# GPduino-R.net
KiCad netlist of a schematic drawn in EAGLE
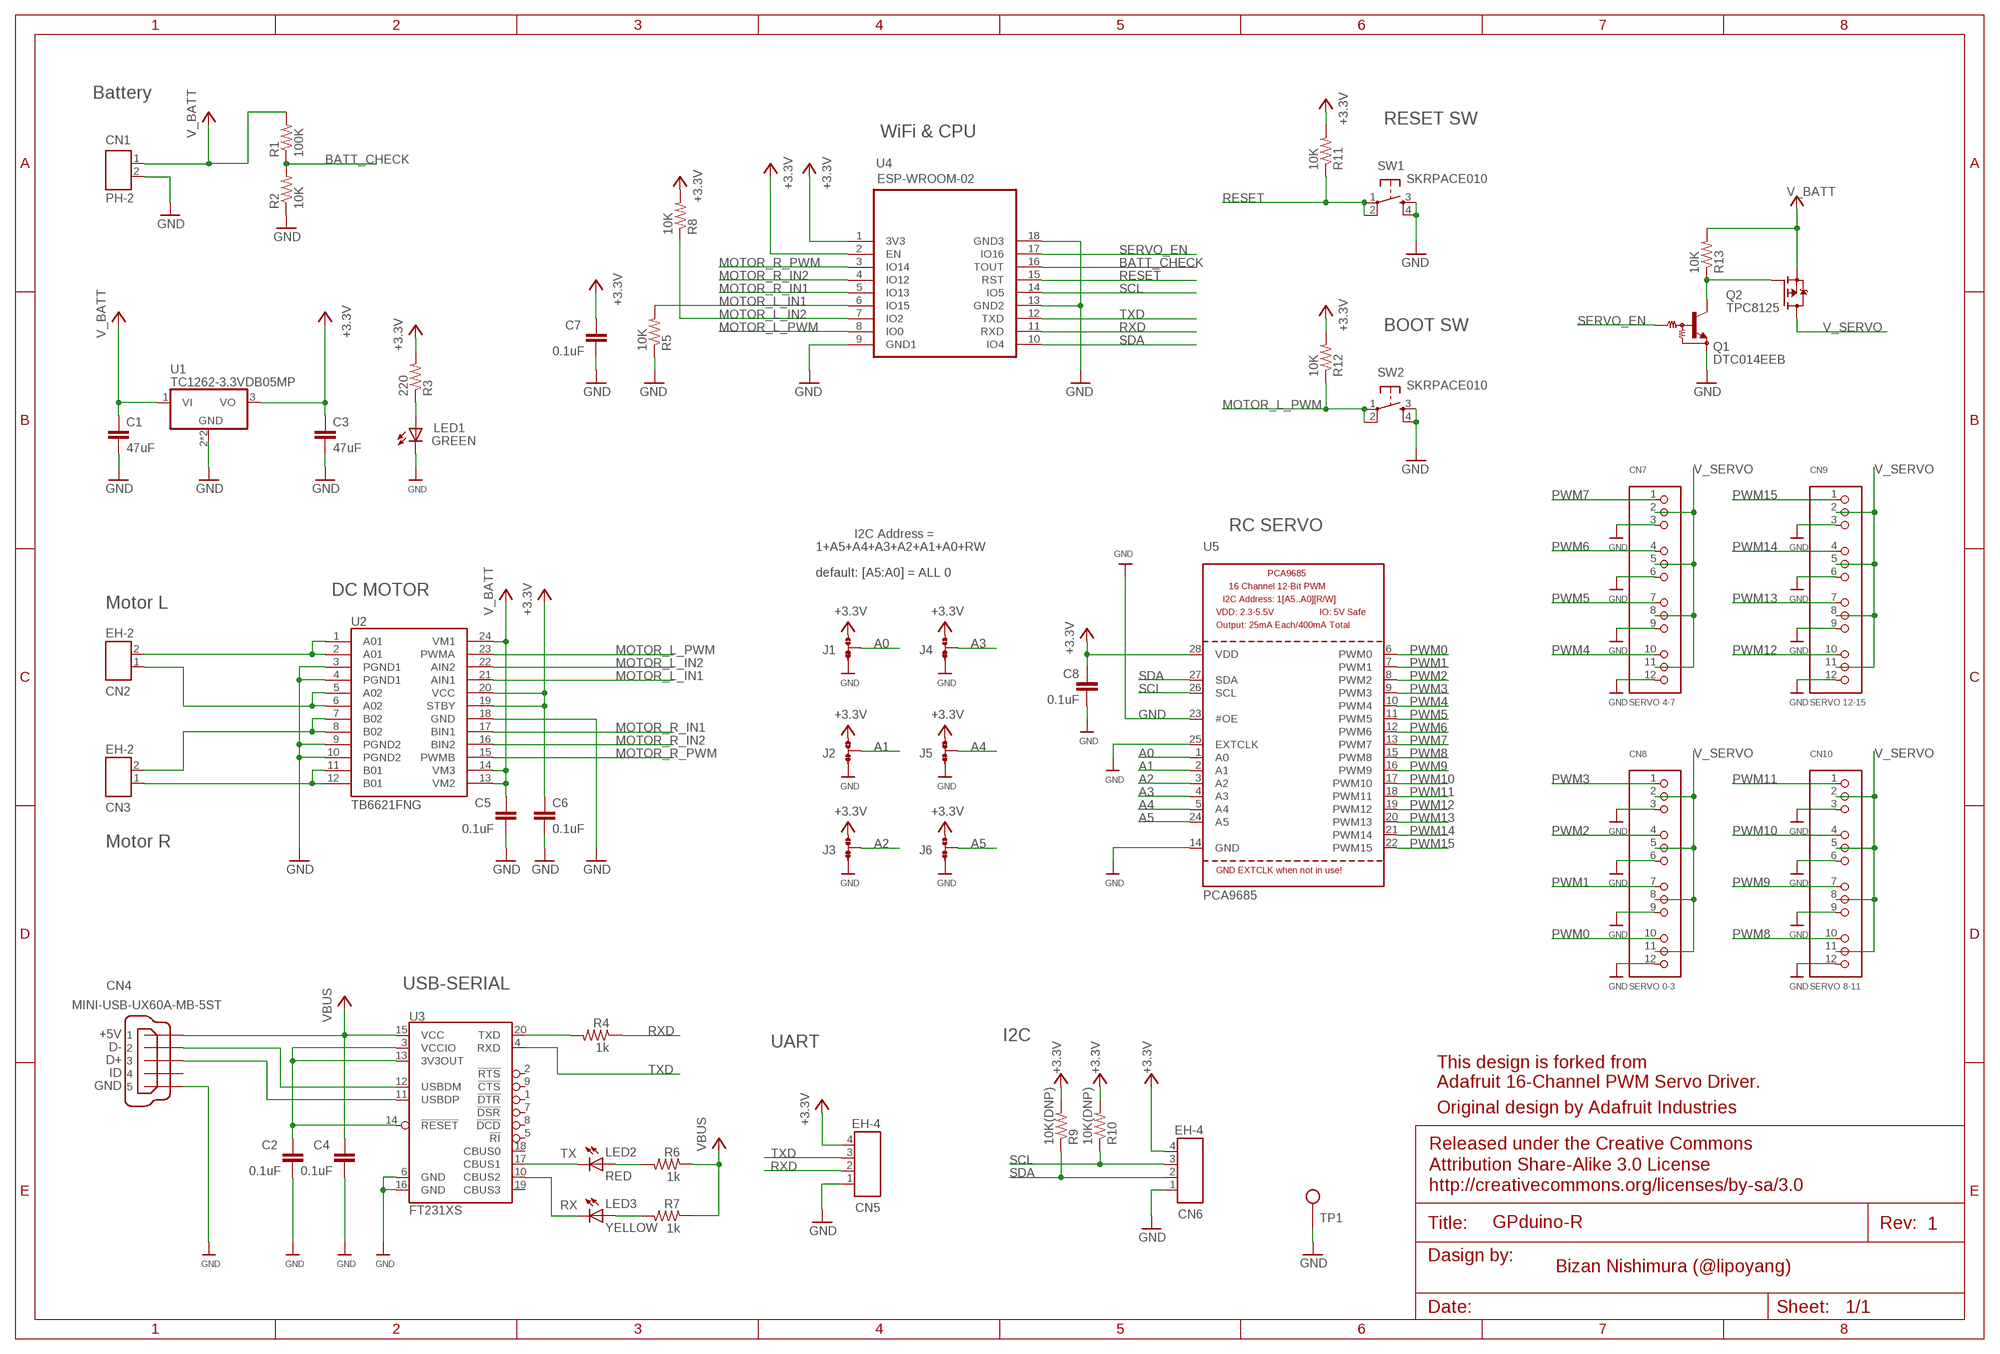
[diagram p0: schematic, sheet 1]

(export (version "E")
  (design (tool "Eeschema 10.0.6"))
  (components
    (comp (ref "C1")
      (value "47uF")
      (footprint "eagle-import:C3216")
      (libsource (lib "eagle-import") (part "C-EUC3216"))
    )
    (comp (ref "C2")
      (value "0.1uF")
      (footprint "eagle-import:C1608")
      (libsource (lib "eagle-import") (part "C-EUC1608"))
    )
    (comp (ref "C3")
      (value "47uF")
      (footprint "eagle-import:C3216")
      (libsource (lib "eagle-import") (part "C-EUC3216"))
    )
    (comp (ref "C4")
      (value "0.1uF")
      (footprint "eagle-import:C1608")
      (libsource (lib "eagle-import") (part "C-EUC1608"))
    )
    (comp (ref "C5")
      (value "0.1uF")
      (footprint "eagle-import:C1608")
      (libsource (lib "eagle-import") (part "C-EUC1608"))
    )
    (comp (ref "C6")
      (value "0.1uF")
      (footprint "eagle-import:C1608")
      (libsource (lib "eagle-import") (part "C-EUC1608"))
    )
    (comp (ref "C7")
      (value "0.1uF")
      (footprint "eagle-import:C1608")
      (libsource (lib "eagle-import") (part "C-EUC1608"))
    )
    (comp (ref "C8")
      (value "0.1uF")
      (footprint "eagle-import:C1608")
      (libsource (lib "eagle-import") (part "C-EUC1608"))
    )
    (comp (ref "CN1")
      (value "PH-2")
      (footprint "eagle-import:PH-2")
      (libsource (lib "eagle-import") (part "PH-2"))
    )
    (comp (ref "CN2")
      (value "EH-2")
      (footprint "eagle-import:EH-2")
      (libsource (lib "eagle-import") (part "EH-2"))
    )
    (comp (ref "CN3")
      (value "EH-2")
      (footprint "eagle-import:EH-2")
      (libsource (lib "eagle-import") (part "EH-2"))
    )
    (comp (ref "CN4")
      (value "MINI-USB-UX60A-MB-5ST")
      (footprint "eagle-import:UX60A-MB-5ST")
      (libsource (lib "eagle-import") (part "MINI-USB-UX60A-MB-5ST"))
    )
    (comp (ref "CN5")
      (value "EH-4")
      (footprint "eagle-import:EH-4")
      (libsource (lib "eagle-import") (part "EH-4"))
    )
    (comp (ref "CN6")
      (value "EH-4")
      (footprint "eagle-import:EH-4")
      (libsource (lib "eagle-import") (part "EH-4"))
    )
    (comp (ref "CN7")
      (value "SERVO 4-7")
      (footprint "eagle-import:3X04")
      (libsource (lib "eagle-import") (part "HEADER-3X04"))
    )
    (comp (ref "CN8")
      (value "SERVO 0-3")
      (footprint "eagle-import:3X04")
      (libsource (lib "eagle-import") (part "HEADER-3X04"))
    )
    (comp (ref "CN9")
      (value "SERVO 12-15")
      (footprint "eagle-import:3X04")
      (libsource (lib "eagle-import") (part "HEADER-3X04"))
    )
    (comp (ref "CN10")
      (value "SERVO 8-11")
      (footprint "eagle-import:3X04")
      (libsource (lib "eagle-import") (part "HEADER-3X04"))
    )
    (comp (ref "J1")
      (value "JUMP-SHORTB")
      (footprint "eagle-import:JUMP-SHORT")
      (libsource (lib "eagle-import") (part "JUMP-SHORTB"))
    )
    (comp (ref "J2")
      (value "JUMP-SHORTB")
      (footprint "eagle-import:JUMP-SHORT")
      (libsource (lib "eagle-import") (part "JUMP-SHORTB"))
    )
    (comp (ref "J3")
      (value "JUMP-SHORTB")
      (footprint "eagle-import:JUMP-SHORT")
      (libsource (lib "eagle-import") (part "JUMP-SHORTB"))
    )
    (comp (ref "J4")
      (value "JUMP-SHORTB")
      (footprint "eagle-import:JUMP-SHORT")
      (libsource (lib "eagle-import") (part "JUMP-SHORTB"))
    )
    (comp (ref "J5")
      (value "JUMP-SHORTB")
      (footprint "eagle-import:JUMP-SHORT")
      (libsource (lib "eagle-import") (part "JUMP-SHORTB"))
    )
    (comp (ref "J6")
      (value "JUMP-SHORTB")
      (footprint "eagle-import:JUMP-SHORT")
      (libsource (lib "eagle-import") (part "JUMP-SHORTB"))
    )
    (comp (ref "LED1")
      (value "GREEN")
      (footprint "eagle-import:CHIPLED_0603")
      (libsource (lib "eagle-import") (part "LEDCHIPLED_0603"))
    )
    (comp (ref "LED2")
      (value "RED")
      (footprint "eagle-import:CHIPLED_0603")
      (libsource (lib "eagle-import") (part "LEDCHIPLED_0603"))
    )
    (comp (ref "LED3")
      (value "YELLOW")
      (footprint "eagle-import:CHIPLED_0603")
      (libsource (lib "eagle-import") (part "LEDCHIPLED_0603"))
    )
    (comp (ref "Q1")
      (value "DTC014EEB")
      (footprint "eagle-import:SOT490")
      (libsource (lib "eagle-import") (part "DIGITORASC89"))
    )
    (comp (ref "Q2")
      (value "TPC8125")
      (footprint "eagle-import:SO-8")
      (libsource (lib "eagle-import") (part "TPC8125"))
    )
    (comp (ref "R1")
      (value "100K")
      (footprint "eagle-import:0603-RES")
      (libsource (lib "eagle-import") (part "RESISTOR0603-RES"))
    )
    (comp (ref "R2")
      (value "10K")
      (footprint "eagle-import:0603-RES")
      (libsource (lib "eagle-import") (part "RESISTOR0603-RES"))
    )
    (comp (ref "R3")
      (value "220")
      (footprint "eagle-import:0603-RES")
      (libsource (lib "eagle-import") (part "RESISTOR0603-RES"))
    )
    (comp (ref "R4")
      (value "1k")
      (footprint "eagle-import:0603-RES")
      (libsource (lib "eagle-import") (part "RESISTOR0603-RES"))
    )
    (comp (ref "R5")
      (value "10K")
      (footprint "eagle-import:0603-RES")
      (libsource (lib "eagle-import") (part "RESISTOR0603-RES"))
    )
    (comp (ref "R6")
      (value "1k")
      (footprint "eagle-import:0603-RES")
      (libsource (lib "eagle-import") (part "RESISTOR0603-RES"))
    )
    (comp (ref "R7")
      (value "1k")
      (footprint "eagle-import:0603-RES")
      (libsource (lib "eagle-import") (part "RESISTOR0603-RES"))
    )
    (comp (ref "R8")
      (value "10K")
      (footprint "eagle-import:0603-RES")
      (libsource (lib "eagle-import") (part "RESISTOR0603-RES"))
    )
    (comp (ref "R9")
      (value "10K(DNP)")
      (footprint "eagle-import:0603-RES")
      (libsource (lib "eagle-import") (part "RESISTOR0603-RES"))
    )
    (comp (ref "R10")
      (value "10K(DNP)")
      (footprint "eagle-import:0603-RES")
      (libsource (lib "eagle-import") (part "RESISTOR0603-RES"))
    )
    (comp (ref "R11")
      (value "10K")
      (footprint "eagle-import:0603-RES")
      (libsource (lib "eagle-import") (part "RESISTOR0603-RES"))
    )
    (comp (ref "R12")
      (value "10K")
      (footprint "eagle-import:0603-RES")
      (libsource (lib "eagle-import") (part "RESISTOR0603-RES"))
    )
    (comp (ref "R13")
      (value "10K")
      (footprint "eagle-import:0603-RES")
      (libsource (lib "eagle-import") (part "RESISTOR0603-RES"))
    )
    (comp (ref "SW1")
      (value "SKRPACE010")
      (footprint "eagle-import:SKRPACE010")
      (libsource (lib "eagle-import") (part "SKRPACE010"))
    )
    (comp (ref "SW2")
      (value "SKRPACE010")
      (footprint "eagle-import:SKRPACE010")
      (libsource (lib "eagle-import") (part "SKRPACE010"))
    )
    (comp (ref "TP1")
      (value "TEST_PIN")
      (footprint "eagle-import:TEST_PIN")
      (libsource (lib "eagle-import") (part "TEST_PIN"))
    )
    (comp (ref "U1")
      (value "TC1262-3.3VDB05MP")
      (footprint "eagle-import:SOT223")
      (libsource (lib "eagle-import") (part "TC1262-3.3VDBMP05"))
    )
    (comp (ref "U2")
      (value "TB6621FNG")
      (footprint "eagle-import:SSOP24")
      (libsource (lib "eagle-import") (part "TB6621FNG"))
    )
    (comp (ref "U3")
      (value "FT231XS")
      (footprint "eagle-import:SSOP20")
      (libsource (lib "eagle-import") (part "FT231XS"))
    )
    (comp (ref "U4")
      (value "ESP-WROOM-02")
      (footprint "eagle-import:FRONT-FACE")
      (libsource (lib "eagle-import") (part "ESP-WROOM-02FRONT-FACE"))
    )
    (comp (ref "U5")
      (value "PCA9685")
      (footprint "eagle-import:TSSOP28")
      (libsource (lib "eagle-import") (part "PCA9685"))
    )
  )
  (nets
    (net (code "1") (name "+3.3V") (class "Default")
      (node (ref "C3") (pin "1") (pinfunction "1_1") (pintype "passive"))
      (node (ref "C6") (pin "1") (pinfunction "1_1") (pintype "passive"))
      (node (ref "C7") (pin "1") (pinfunction "1_1") (pintype "passive"))
      (node (ref "C8") (pin "1") (pinfunction "1_1") (pintype "passive"))
      (node (ref "CN5") (pin "4") (pinfunction "4_4") (pintype "bidirectional"))
      (node (ref "CN6") (pin "4") (pinfunction "4_4") (pintype "bidirectional"))
      (node (ref "J1") (pin "1") (pinfunction "1_1") (pintype "passive"))
      (node (ref "J2") (pin "1") (pinfunction "1_1") (pintype "passive"))
      (node (ref "J3") (pin "1") (pinfunction "1_1") (pintype "passive"))
      (node (ref "J4") (pin "1") (pinfunction "1_1") (pintype "passive"))
      (node (ref "J5") (pin "1") (pinfunction "1_1") (pintype "passive"))
      (node (ref "J6") (pin "1") (pinfunction "1_1") (pintype "passive"))
      (node (ref "R10") (pin "2") (pinfunction "2_2") (pintype "passive"))
      (node (ref "R11") (pin "2") (pinfunction "2_2") (pintype "passive"))
      (node (ref "R12") (pin "2") (pinfunction "2_2") (pintype "passive"))
      (node (ref "R3") (pin "2") (pinfunction "2_2") (pintype "passive"))
      (node (ref "R8") (pin "2") (pinfunction "2_2") (pintype "passive"))
      (node (ref "R9") (pin "2") (pinfunction "2_2") (pintype "passive"))
      (node (ref "U1") (pin "3") (pinfunction "VO_3") (pintype "passive"))
      (node (ref "U2") (pin "19") (pinfunction "STBY_19") (pintype "bidirectional"))
      (node (ref "U2") (pin "20") (pinfunction "VCC_20") (pintype "bidirectional"))
      (node (ref "U4") (pin "1") (pinfunction "3V3_1") (pintype "power_in"))
      (node (ref "U4") (pin "2") (pinfunction "EN_2") (pintype "bidirectional"))
      (node (ref "U5") (pin "28") (pinfunction "VDD_28") (pintype "power_in"))
    )
    (net (code "2") (name "/A0") (class "Default")
      (node (ref "J1") (pin "2") (pinfunction "2_2") (pintype "passive"))
      (node (ref "U5") (pin "1") (pinfunction "A0_1") (pintype "bidirectional"))
    )
    (net (code "3") (name "/A1") (class "Default")
      (node (ref "J2") (pin "2") (pinfunction "2_2") (pintype "passive"))
      (node (ref "U5") (pin "2") (pinfunction "A1_2") (pintype "bidirectional"))
    )
    (net (code "4") (name "/A2") (class "Default")
      (node (ref "J3") (pin "2") (pinfunction "2_2") (pintype "passive"))
      (node (ref "U5") (pin "3") (pinfunction "A2_3") (pintype "bidirectional"))
    )
    (net (code "5") (name "/A3") (class "Default")
      (node (ref "J4") (pin "2") (pinfunction "2_2") (pintype "passive"))
      (node (ref "U5") (pin "4") (pinfunction "A3_4") (pintype "bidirectional"))
    )
    (net (code "6") (name "/A4") (class "Default")
      (node (ref "J5") (pin "2") (pinfunction "2_2") (pintype "passive"))
      (node (ref "U5") (pin "5") (pinfunction "A4_5") (pintype "bidirectional"))
    )
    (net (code "7") (name "/A5") (class "Default")
      (node (ref "J6") (pin "2") (pinfunction "2_2") (pintype "passive"))
      (node (ref "U5") (pin "24") (pinfunction "A5_24") (pintype "bidirectional"))
    )
    (net (code "8") (name "/BATT_CHECK") (class "Default")
      (node (ref "R1") (pin "1") (pinfunction "1_1") (pintype "passive"))
      (node (ref "R2") (pin "2") (pinfunction "2_2") (pintype "passive"))
      (node (ref "U4") (pin "16") (pinfunction "TOUT_16") (pintype "bidirectional"))
    )
    (net (code "9") (name "/MOTOR_L_IN1") (class "Default")
      (node (ref "R5") (pin "2") (pinfunction "2_2") (pintype "passive"))
      (node (ref "U2") (pin "21") (pinfunction "AIN1_21") (pintype "bidirectional"))
      (node (ref "U4") (pin "6") (pinfunction "IO15_6") (pintype "bidirectional"))
    )
    (net (code "10") (name "/MOTOR_L_IN2") (class "Default")
      (node (ref "R8") (pin "1") (pinfunction "1_1") (pintype "passive"))
      (node (ref "U2") (pin "22") (pinfunction "AIN2_22") (pintype "bidirectional"))
      (node (ref "U4") (pin "7") (pinfunction "IO2_7") (pintype "bidirectional"))
    )
    (net (code "11") (name "/MOTOR_L_PWM") (class "Default")
      (node (ref "R12") (pin "1") (pinfunction "1_1") (pintype "passive"))
      (node (ref "SW2") (pin "1") (pinfunction "1_1") (pintype "passive"))
      (node (ref "SW2") (pin "2") (pinfunction "2_2") (pintype "passive"))
      (node (ref "U2") (pin "23") (pinfunction "PWMA_23") (pintype "bidirectional"))
      (node (ref "U4") (pin "8") (pinfunction "IO0_8") (pintype "bidirectional"))
    )
    (net (code "12") (name "/MOTOR_R_IN1") (class "Default")
      (node (ref "U2") (pin "17") (pinfunction "BIN1_17") (pintype "bidirectional"))
      (node (ref "U4") (pin "5") (pinfunction "IO13_5") (pintype "bidirectional"))
    )
    (net (code "13") (name "/MOTOR_R_IN2") (class "Default")
      (node (ref "U2") (pin "16") (pinfunction "BIN2_16") (pintype "bidirectional"))
      (node (ref "U4") (pin "4") (pinfunction "IO12_4") (pintype "bidirectional"))
    )
    (net (code "14") (name "/MOTOR_R_PWM") (class "Default")
      (node (ref "U2") (pin "15") (pinfunction "PWMB_15") (pintype "bidirectional"))
      (node (ref "U4") (pin "3") (pinfunction "IO14_3") (pintype "bidirectional"))
    )
    (net (code "15") (name "/PWM0") (class "Default")
      (node (ref "CN8") (pin "10") (pinfunction "10_10") (pintype "passive"))
      (node (ref "U5") (pin "6") (pinfunction "PWM0_6") (pintype "output"))
    )
    (net (code "16") (name "/PWM1") (class "Default")
      (node (ref "CN8") (pin "7") (pinfunction "7_7") (pintype "passive"))
      (node (ref "U5") (pin "7") (pinfunction "PWM1_7") (pintype "output"))
    )
    (net (code "17") (name "/PWM2") (class "Default")
      (node (ref "CN8") (pin "4") (pinfunction "4_4") (pintype "passive"))
      (node (ref "U5") (pin "8") (pinfunction "PWM2_8") (pintype "output"))
    )
    (net (code "18") (name "/PWM3") (class "Default")
      (node (ref "CN8") (pin "1") (pinfunction "1_1") (pintype "passive"))
      (node (ref "U5") (pin "9") (pinfunction "PWM3_9") (pintype "output"))
    )
    (net (code "19") (name "/PWM4") (class "Default")
      (node (ref "CN7") (pin "10") (pinfunction "10_10") (pintype "passive"))
      (node (ref "U5") (pin "10") (pinfunction "PWM4_10") (pintype "output"))
    )
    (net (code "20") (name "/PWM5") (class "Default")
      (node (ref "CN7") (pin "7") (pinfunction "7_7") (pintype "passive"))
      (node (ref "U5") (pin "11") (pinfunction "PWM5_11") (pintype "output"))
    )
    (net (code "21") (name "/PWM6") (class "Default")
      (node (ref "CN7") (pin "4") (pinfunction "4_4") (pintype "passive"))
      (node (ref "U5") (pin "12") (pinfunction "PWM6_12") (pintype "output"))
    )
    (net (code "22") (name "/PWM7") (class "Default")
      (node (ref "CN7") (pin "1") (pinfunction "1_1") (pintype "passive"))
      (node (ref "U5") (pin "13") (pinfunction "PWM7_13") (pintype "output"))
    )
    (net (code "23") (name "/PWM8") (class "Default")
      (node (ref "CN10") (pin "10") (pinfunction "10_10") (pintype "passive"))
      (node (ref "U5") (pin "15") (pinfunction "PWM8_15") (pintype "output"))
    )
    (net (code "24") (name "/PWM9") (class "Default")
      (node (ref "CN10") (pin "7") (pinfunction "7_7") (pintype "passive"))
      (node (ref "U5") (pin "16") (pinfunction "PWM9_16") (pintype "output"))
    )
    (net (code "25") (name "/PWM10") (class "Default")
      (node (ref "CN10") (pin "4") (pinfunction "4_4") (pintype "passive"))
      (node (ref "U5") (pin "17") (pinfunction "PWM10_17") (pintype "output"))
    )
    (net (code "26") (name "/PWM11") (class "Default")
      (node (ref "CN10") (pin "1") (pinfunction "1_1") (pintype "passive"))
      (node (ref "U5") (pin "18") (pinfunction "PWM11_18") (pintype "output"))
    )
    (net (code "27") (name "/PWM12") (class "Default")
      (node (ref "CN9") (pin "10") (pinfunction "10_10") (pintype "passive"))
      (node (ref "U5") (pin "19") (pinfunction "PWM12_19") (pintype "output"))
    )
    (net (code "28") (name "/PWM13") (class "Default")
      (node (ref "CN9") (pin "7") (pinfunction "7_7") (pintype "passive"))
      (node (ref "U5") (pin "20") (pinfunction "PWM13_20") (pintype "output"))
    )
    (net (code "29") (name "/PWM14") (class "Default")
      (node (ref "CN9") (pin "4") (pinfunction "4_4") (pintype "passive"))
      (node (ref "U5") (pin "21") (pinfunction "PWM14_21") (pintype "output"))
    )
    (net (code "30") (name "/PWM15") (class "Default")
      (node (ref "CN9") (pin "1") (pinfunction "1_1") (pintype "passive"))
      (node (ref "U5") (pin "22") (pinfunction "PWM15_22") (pintype "output"))
    )
    (net (code "31") (name "/RESET") (class "Default")
      (node (ref "R11") (pin "1") (pinfunction "1_1") (pintype "passive"))
      (node (ref "SW1") (pin "1") (pinfunction "1_1") (pintype "passive"))
      (node (ref "SW1") (pin "2") (pinfunction "2_2") (pintype "passive"))
      (node (ref "U4") (pin "15") (pinfunction "RST_15") (pintype "bidirectional"))
    )
    (net (code "32") (name "/RXD") (class "Default")
      (node (ref "CN5") (pin "2") (pinfunction "2_2") (pintype "bidirectional"))
      (node (ref "R4") (pin "1") (pinfunction "1_1") (pintype "passive"))
      (node (ref "U4") (pin "11") (pinfunction "RXD_11") (pintype "bidirectional"))
    )
    (net (code "33") (name "/SCL") (class "Default")
      (node (ref "CN6") (pin "3") (pinfunction "3_3") (pintype "bidirectional"))
      (node (ref "R10") (pin "1") (pinfunction "1_1") (pintype "passive"))
      (node (ref "U4") (pin "14") (pinfunction "IO5_14") (pintype "open_collector"))
      (node (ref "U5") (pin "26") (pinfunction "SCL_26") (pintype "bidirectional"))
    )
    (net (code "34") (name "/SDA") (class "Default")
      (node (ref "CN6") (pin "2") (pinfunction "2_2") (pintype "bidirectional"))
      (node (ref "R9") (pin "1") (pinfunction "1_1") (pintype "passive"))
      (node (ref "U4") (pin "10") (pinfunction "IO4_10") (pintype "bidirectional"))
      (node (ref "U5") (pin "27") (pinfunction "SDA_27") (pintype "bidirectional"))
    )
    (net (code "35") (name "/SERVO_EN") (class "Default")
      (node (ref "Q1") (pin "1") (pinfunction "B_1") (pintype "passive"))
      (node (ref "U4") (pin "17") (pinfunction "IO16_17") (pintype "bidirectional"))
    )
    (net (code "36") (name "/TXD") (class "Default")
      (node (ref "CN5") (pin "3") (pinfunction "3_3") (pintype "bidirectional"))
      (node (ref "U3") (pin "4") (pinfunction "RXD_4") (pintype "bidirectional"))
      (node (ref "U4") (pin "12") (pinfunction "TXD_12") (pintype "bidirectional"))
    )
    (net (code "37") (name "/V_SERVO") (class "Default")
      (node (ref "CN10") (pin "11") (pinfunction "11_11") (pintype "passive"))
      (node (ref "CN10") (pin "2") (pinfunction "2_2") (pintype "passive"))
      (node (ref "CN10") (pin "5") (pinfunction "5_5") (pintype "passive"))
      (node (ref "CN10") (pin "8") (pinfunction "8_8") (pintype "passive"))
      (node (ref "CN7") (pin "11") (pinfunction "11_11") (pintype "passive"))
      (node (ref "CN7") (pin "2") (pinfunction "2_2") (pintype "passive"))
      (node (ref "CN7") (pin "5") (pinfunction "5_5") (pintype "passive"))
      (node (ref "CN7") (pin "8") (pinfunction "8_8") (pintype "passive"))
      (node (ref "CN8") (pin "11") (pinfunction "11_11") (pintype "passive"))
      (node (ref "CN8") (pin "2") (pinfunction "2_2") (pintype "passive"))
      (node (ref "CN8") (pin "5") (pinfunction "5_5") (pintype "passive"))
      (node (ref "CN8") (pin "8") (pinfunction "8_8") (pintype "passive"))
      (node (ref "CN9") (pin "11") (pinfunction "11_11") (pintype "passive"))
      (node (ref "CN9") (pin "2") (pinfunction "2_2") (pintype "passive"))
      (node (ref "CN9") (pin "5") (pinfunction "5_5") (pintype "passive"))
      (node (ref "CN9") (pin "8") (pinfunction "8_8") (pintype "passive"))
      (node (ref "Q2") (pin "5") (pinfunction "D_5") (pintype "passive"))
      (node (ref "Q2") (pin "6") (pinfunction "D_6") (pintype "passive"))
      (node (ref "Q2") (pin "7") (pinfunction "D_7") (pintype "passive"))
      (node (ref "Q2") (pin "8") (pinfunction "D_8") (pintype "passive"))
    )
    (net (code "38") (name "GND") (class "Default")
      (node (ref "C1") (pin "2") (pinfunction "2_2") (pintype "passive"))
      (node (ref "C2") (pin "2") (pinfunction "2_2") (pintype "passive"))
      (node (ref "C3") (pin "2") (pinfunction "2_2") (pintype "passive"))
      (node (ref "C4") (pin "2") (pinfunction "2_2") (pintype "passive"))
      (node (ref "C5") (pin "2") (pinfunction "2_2") (pintype "passive"))
      (node (ref "C6") (pin "2") (pinfunction "2_2") (pintype "passive"))
      (node (ref "C7") (pin "2") (pinfunction "2_2") (pintype "passive"))
      (node (ref "C8") (pin "2") (pinfunction "2_2") (pintype "passive"))
      (node (ref "CN1") (pin "2") (pinfunction "2_2") (pintype "bidirectional"))
      (node (ref "CN10") (pin "12") (pinfunction "12_12") (pintype "passive"))
      (node (ref "CN10") (pin "3") (pinfunction "3_3") (pintype "passive"))
      (node (ref "CN10") (pin "6") (pinfunction "6_6") (pintype "passive"))
      (node (ref "CN10") (pin "9") (pinfunction "9_9") (pintype "passive"))
      (node (ref "CN4") (pin "5") (pinfunction "5_5") (pintype "input"))
      (node (ref "CN5") (pin "1") (pinfunction "1_1") (pintype "bidirectional"))
      (node (ref "CN6") (pin "1") (pinfunction "1_1") (pintype "bidirectional"))
      (node (ref "CN7") (pin "12") (pinfunction "12_12") (pintype "passive"))
      (node (ref "CN7") (pin "3") (pinfunction "3_3") (pintype "passive"))
      (node (ref "CN7") (pin "6") (pinfunction "6_6") (pintype "passive"))
      (node (ref "CN7") (pin "9") (pinfunction "9_9") (pintype "passive"))
      (node (ref "CN8") (pin "12") (pinfunction "12_12") (pintype "passive"))
      (node (ref "CN8") (pin "3") (pinfunction "3_3") (pintype "passive"))
      (node (ref "CN8") (pin "6") (pinfunction "6_6") (pintype "passive"))
      (node (ref "CN8") (pin "9") (pinfunction "9_9") (pintype "passive"))
      (node (ref "CN9") (pin "12") (pinfunction "12_12") (pintype "passive"))
      (node (ref "CN9") (pin "3") (pinfunction "3_3") (pintype "passive"))
      (node (ref "CN9") (pin "6") (pinfunction "6_6") (pintype "passive"))
      (node (ref "CN9") (pin "9") (pinfunction "9_9") (pintype "passive"))
      (node (ref "J1") (pin "3") (pinfunction "3_3") (pintype "passive"))
      (node (ref "J2") (pin "3") (pinfunction "3_3") (pintype "passive"))
      (node (ref "J3") (pin "3") (pinfunction "3_3") (pintype "passive"))
      (node (ref "J4") (pin "3") (pinfunction "3_3") (pintype "passive"))
      (node (ref "J5") (pin "3") (pinfunction "3_3") (pintype "passive"))
      (node (ref "J6") (pin "3") (pinfunction "3_3") (pintype "passive"))
      (node (ref "LED1") (pin "C") (pinfunction "C_C") (pintype "passive"))
      (node (ref "Q1") (pin "2") (pinfunction "E_2") (pintype "passive"))
      (node (ref "R2") (pin "1") (pinfunction "1_1") (pintype "passive"))
      (node (ref "R5") (pin "1") (pinfunction "1_1") (pintype "passive"))
      (node (ref "SW1") (pin "3") (pinfunction "3_3") (pintype "passive"))
      (node (ref "SW1") (pin "4") (pinfunction "4_4") (pintype "passive"))
      (node (ref "SW2") (pin "3") (pinfunction "3_3") (pintype "passive"))
      (node (ref "SW2") (pin "4") (pinfunction "4_4") (pintype "passive"))
      (node (ref "TP1") (pin "1") (pinfunction "P$1_1") (pintype "bidirectional"))
      (node (ref "U1") (pin "2") (pinfunction "GND_2") (pintype "passive"))
      (node (ref "U1") (pin "4") (pinfunction "GND_4") (pintype "passive"))
      (node (ref "U2") (pin "10") (pinfunction "PGND2_10") (pintype "bidirectional"))
      (node (ref "U2") (pin "18") (pinfunction "GND_18") (pintype "bidirectional"))
      (node (ref "U2") (pin "3") (pinfunction "PGND1_3") (pintype "bidirectional"))
      (node (ref "U2") (pin "4") (pinfunction "PGND1_4") (pintype "bidirectional"))
      (node (ref "U2") (pin "9") (pinfunction "PGND2_9") (pintype "bidirectional"))
      (node (ref "U3") (pin "16") (pinfunction "GND_16") (pintype "bidirectional"))
      (node (ref "U3") (pin "6") (pinfunction "GND_6") (pintype "bidirectional"))
      (node (ref "U4") (pin "13") (pinfunction "GND2_13") (pintype "power_in"))
      (node (ref "U4") (pin "18") (pinfunction "GND3_18") (pintype "power_in"))
      (node (ref "U4") (pin "9") (pinfunction "GND1_9") (pintype "power_in"))
      (node (ref "U5") (pin "14") (pinfunction "GND_14") (pintype "power_in"))
      (node (ref "U5") (pin "23") (pinfunction "#OE_23") (pintype "input"))
      (node (ref "U5") (pin "25") (pinfunction "EXTCLK_25") (pintype "input"))
    )
    (net (code "39") (name "Net-(CN2-Pad1)") (class "Default")
      (node (ref "CN2") (pin "1") (pinfunction "1_1") (pintype "bidirectional"))
      (node (ref "U2") (pin "5") (pinfunction "A02_5") (pintype "bidirectional"))
      (node (ref "U2") (pin "6") (pinfunction "A02_6") (pintype "bidirectional"))
    )
    (net (code "40") (name "Net-(CN2-Pad2)") (class "Default")
      (node (ref "CN2") (pin "2") (pinfunction "2_2") (pintype "bidirectional"))
      (node (ref "U2") (pin "1") (pinfunction "A01_1") (pintype "bidirectional"))
      (node (ref "U2") (pin "2") (pinfunction "A01_2") (pintype "bidirectional"))
    )
    (net (code "41") (name "Net-(CN3-Pad1)") (class "Default")
      (node (ref "CN3") (pin "1") (pinfunction "1_1") (pintype "bidirectional"))
      (node (ref "U2") (pin "11") (pinfunction "B01_11") (pintype "bidirectional"))
      (node (ref "U2") (pin "12") (pinfunction "B01_12") (pintype "bidirectional"))
    )
    (net (code "42") (name "Net-(CN3-Pad2)") (class "Default")
      (node (ref "CN3") (pin "2") (pinfunction "2_2") (pintype "bidirectional"))
      (node (ref "U2") (pin "7") (pinfunction "B02_7") (pintype "bidirectional"))
      (node (ref "U2") (pin "8") (pinfunction "B02_8") (pintype "bidirectional"))
    )
    (net (code "43") (name "Net-(LED1-PadA)") (class "Default")
      (node (ref "LED1") (pin "A") (pinfunction "A_A") (pintype "passive"))
      (node (ref "R3") (pin "1") (pinfunction "1_1") (pintype "passive"))
    )
    (net (code "44") (name "Net-(LED2-PadA)") (class "Default")
      (node (ref "LED2") (pin "A") (pinfunction "A_A") (pintype "passive"))
      (node (ref "R6") (pin "2") (pinfunction "2_2") (pintype "passive"))
    )
    (net (code "45") (name "Net-(LED3-PadA)") (class "Default")
      (node (ref "LED3") (pin "A") (pinfunction "A_A") (pintype "passive"))
      (node (ref "R7") (pin "2") (pinfunction "2_2") (pintype "passive"))
    )
    (net (code "46") (name "Net-(Q1-C)") (class "Default")
      (node (ref "Q1") (pin "3") (pinfunction "C_3") (pintype "passive"))
      (node (ref "Q2") (pin "4") (pinfunction "G_4") (pintype "passive"))
      (node (ref "R13") (pin "1") (pinfunction "1_1") (pintype "passive"))
    )
    (net (code "47") (name "Net-(U3-3V3OUT)") (class "Default")
      (node (ref "C2") (pin "1") (pinfunction "1_1") (pintype "passive"))
      (node (ref "U3") (pin "13") (pinfunction "3V3OUT_13") (pintype "bidirectional"))
      (node (ref "U3") (pin "14") (pinfunction "~{RESET}_14") (pintype "bidirectional"))
      (node (ref "U3") (pin "3") (pinfunction "VCCIO_3") (pintype "bidirectional"))
    )
    (net (code "48") (name "Net-(U3-CBUS1)") (class "Default")
      (node (ref "LED2") (pin "C") (pinfunction "C_C") (pintype "passive"))
      (node (ref "U3") (pin "17") (pinfunction "CBUS1_17") (pintype "bidirectional"))
    )
    (net (code "49") (name "Net-(U3-CBUS2)") (class "Default")
      (node (ref "LED3") (pin "C") (pinfunction "C_C") (pintype "passive"))
      (node (ref "U3") (pin "10") (pinfunction "CBUS2_10") (pintype "bidirectional"))
    )
    (net (code "50") (name "Net-(U3-TXD)") (class "Default")
      (node (ref "R4") (pin "2") (pinfunction "2_2") (pintype "passive"))
      (node (ref "U3") (pin "20") (pinfunction "TXD_20") (pintype "bidirectional"))
    )
    (net (code "51") (name "Net-(U3-USBDM)") (class "Default")
      (node (ref "CN4") (pin "2") (pinfunction "2_2") (pintype "input"))
      (node (ref "U3") (pin "12") (pinfunction "USBDM_12") (pintype "bidirectional"))
    )
    (net (code "52") (name "Net-(U3-USBDP)") (class "Default")
      (node (ref "CN4") (pin "3") (pinfunction "3_3") (pintype "input"))
      (node (ref "U3") (pin "11") (pinfunction "USBDP_11") (pintype "bidirectional"))
    )
    (net (code "53") (name "VBUS") (class "Default")
      (node (ref "C4") (pin "1") (pinfunction "1_1") (pintype "passive"))
      (node (ref "CN4") (pin "1") (pinfunction "1_1") (pintype "input"))
      (node (ref "R6") (pin "1") (pinfunction "1_1") (pintype "passive"))
      (node (ref "R7") (pin "1") (pinfunction "1_1") (pintype "passive"))
      (node (ref "U3") (pin "15") (pinfunction "VCC_15") (pintype "bidirectional"))
    )
    (net (code "54") (name "V_BATT") (class "Default")
      (node (ref "C1") (pin "1") (pinfunction "1_1") (pintype "passive"))
      (node (ref "C5") (pin "1") (pinfunction "1_1") (pintype "passive"))
      (node (ref "CN1") (pin "1") (pinfunction "1_1") (pintype "bidirectional"))
      (node (ref "Q2") (pin "1") (pinfunction "S_1") (pintype "passive"))
      (node (ref "Q2") (pin "2") (pinfunction "S_2") (pintype "passive"))
      (node (ref "Q2") (pin "3") (pinfunction "S_3") (pintype "passive"))
      (node (ref "R1") (pin "2") (pinfunction "2_2") (pintype "passive"))
      (node (ref "R13") (pin "2") (pinfunction "2_2") (pintype "passive"))
      (node (ref "U1") (pin "1") (pinfunction "VI_1") (pintype "input"))
      (node (ref "U2") (pin "13") (pinfunction "VM2_13") (pintype "bidirectional"))
      (node (ref "U2") (pin "14") (pinfunction "VM3_14") (pintype "bidirectional"))
      (node (ref "U2") (pin "24") (pinfunction "VM1_24") (pintype "bidirectional"))
    )
    (net (code "55") (name "unconnected-(CN4-Pad4)") (class "Default")
      (node (ref "CN4") (pin "4") (pinfunction "4_4") (pintype "input"))
    )
    (net (code "56") (name "unconnected-(U3-CBUS0-Pad18)") (class "Default")
      (node (ref "U3") (pin "18") (pinfunction "CBUS0_18") (pintype "bidirectional"))
    )
    (net (code "57") (name "unconnected-(U3-CBUS3-Pad19)") (class "Default")
      (node (ref "U3") (pin "19") (pinfunction "CBUS3_19") (pintype "bidirectional"))
    )
    (net (code "58") (name "unconnected-(U3-~{CTS}-Pad9)") (class "Default")
      (node (ref "U3") (pin "9") (pinfunction "~{CTS}_9") (pintype "bidirectional"))
    )
    (net (code "59") (name "unconnected-(U3-~{DCD}-Pad8)") (class "Default")
      (node (ref "U3") (pin "8") (pinfunction "~{DCD}_8") (pintype "bidirectional"))
    )
    (net (code "60") (name "unconnected-(U3-~{DSR}-Pad7)") (class "Default")
      (node (ref "U3") (pin "7") (pinfunction "~{DSR}_7") (pintype "bidirectional"))
    )
    (net (code "61") (name "unconnected-(U3-~{DTR}-Pad1)") (class "Default")
      (node (ref "U3") (pin "1") (pinfunction "~{DTR}_1") (pintype "bidirectional"))
    )
    (net (code "62") (name "unconnected-(U3-~{RI}-Pad5)") (class "Default")
      (node (ref "U3") (pin "5") (pinfunction "~{RI}_5") (pintype "bidirectional"))
    )
    (net (code "63") (name "unconnected-(U3-~{RTS}-Pad2)") (class "Default")
      (node (ref "U3") (pin "2") (pinfunction "~{RTS}_2") (pintype "bidirectional"))
    )
  )
)
